# 01_Main.net
KiCad netlist of a schematic drawn in Altium Designer
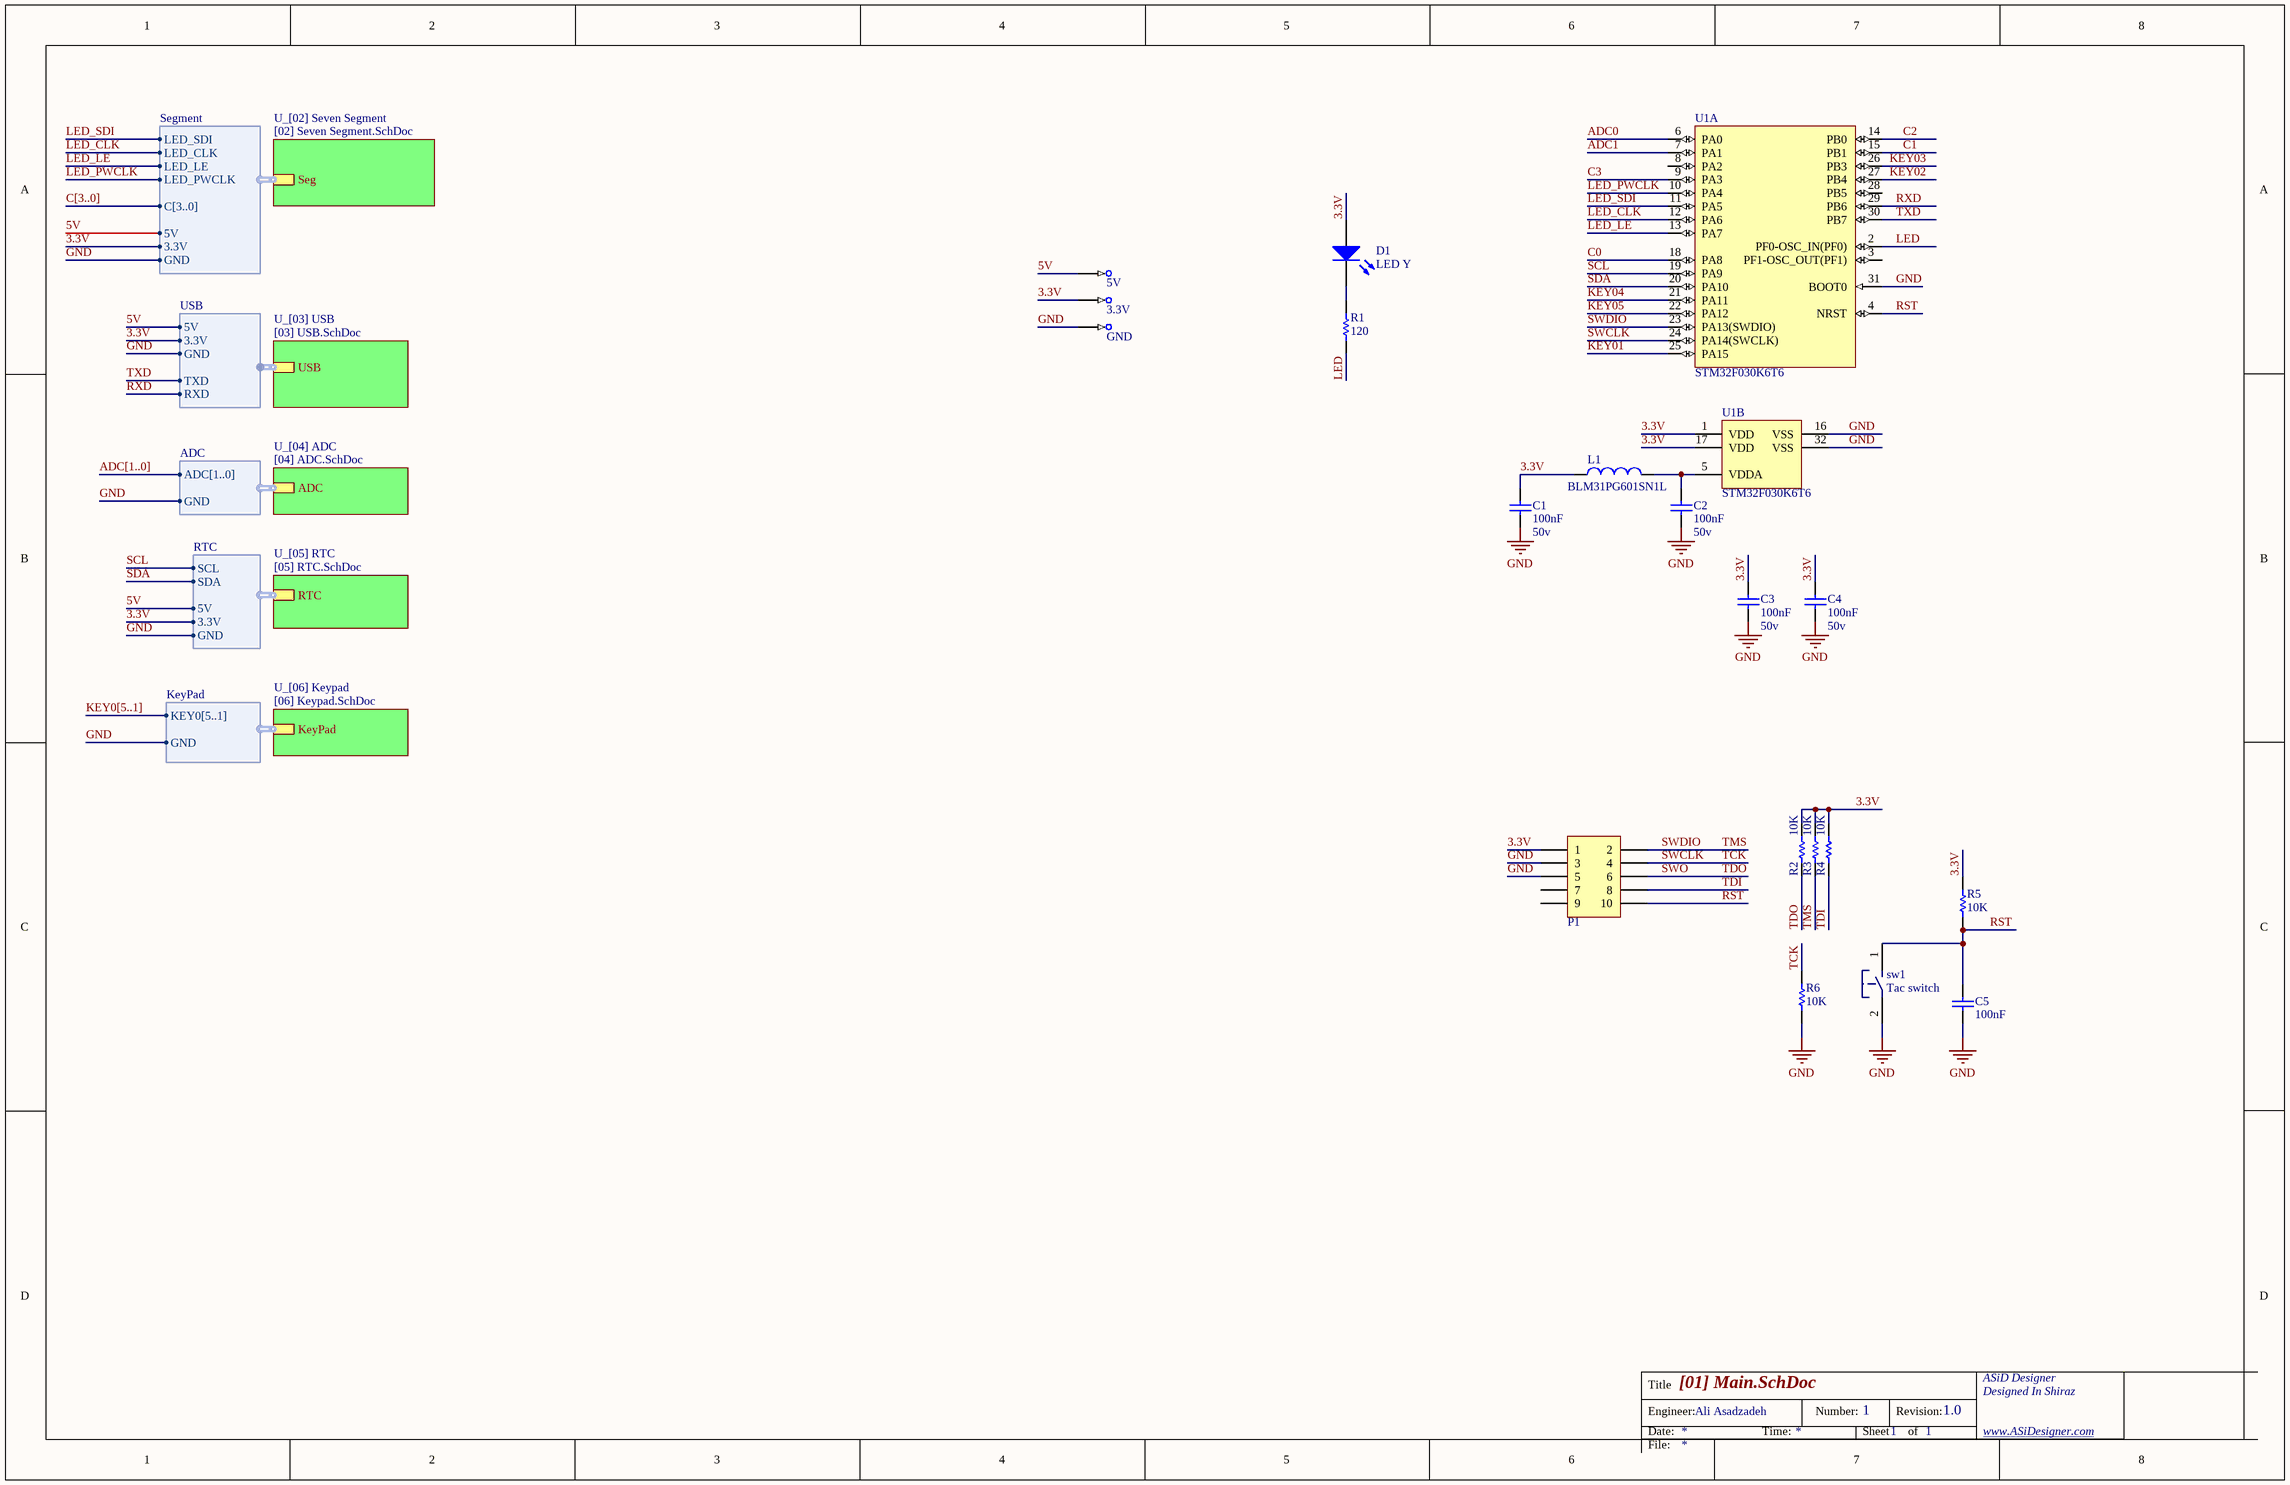
[diagram p0: [01] Main.SchDoc]

(export (version "E")
  (design (tool "Eeschema 10.0.6"))
  (components
    (comp (ref "C1")
      (value "100nF")
      (footprint "MY_0603")
      (description "None polar capacitor")
      (fields (field (name "ASID PART NUMBER") "C-AS") (field (name "VOLTE") "50v"))
      (libsource (lib "Mylib Rev 4") (part "Cap ceramic"))
    )
    (comp (ref "C2")
      (value "100nF")
      (footprint "MY_0603")
      (description "None polar capacitor")
      (fields (field (name "ASID PART NUMBER") "C-AS") (field (name "VOLTE") "50v"))
      (libsource (lib "Mylib Rev 4") (part "Cap ceramic"))
    )
    (comp (ref "C3")
      (value "100nF")
      (footprint "MY_0603")
      (description "None polar capacitor")
      (fields (field (name "ASID PART NUMBER") "C-AS") (field (name "VOLTE") "50v"))
      (libsource (lib "Mylib Rev 4") (part "Cap ceramic"))
    )
    (comp (ref "C4")
      (value "100nF")
      (footprint "MY_0603")
      (description "None polar capacitor")
      (fields (field (name "ASID PART NUMBER") "C-AS") (field (name "VOLTE") "50v"))
      (libsource (lib "Mylib Rev 4") (part "Cap ceramic"))
    )
    (comp (ref "C5")
      (value "100nF")
      (footprint "MY_0805")
      (description "CAP-100Nf")
      (libsource (lib "Mylib Rev 4") (part "Cap ceramic"))
    )
    (comp (ref "D1")
      (value "LED Y")
      (footprint "MY_LED_0805")
      (description "Typical INFRARED GaAs LED")
      (fields (field (name "ASID PART NUMBER") "LED-AS"))
      (libsource (lib "Mylib Rev 4") (part "LED"))
    )
    (comp (ref "L1")
      (value "BLM31PG601SN1L")
      (footprint "MY_1206")
      (description "Inductor")
      (fields (field (name "ASID PART NUMBER") "Inductor-AS"))
      (libsource (lib "Mylib Rev 4") (part "Inductor"))
    )
    (comp (ref "P1")
      (value "Header 5X2")
      (footprint "MY_2X05_BOX")
      (description "Header, 10-Pin, Dual row")
      (fields (field (name "ASID PART NUMBER") "Header 5X2-AS"))
      (libsource (lib "Mylib Rev 4") (part "Header 5X2"))
    )
    (comp (ref "R1")
      (value "120")
      (footprint "MY_0805")
      (description "Standard resistor")
      (fields (field (name "ASID PART NUMBER") "Res-AS"))
      (libsource (lib "Mylib Rev 4") (part "Res"))
    )
    (comp (ref "R2")
      (value "10K")
      (footprint "MY_0805")
      (description "resistor 1/4 wat")
      (libsource (lib "Mylib Rev 4") (part "Res"))
    )
    (comp (ref "R3")
      (value "10K")
      (footprint "MY_0805")
      (description "resistor 1/4 wat")
      (libsource (lib "Mylib Rev 4") (part "Res"))
    )
    (comp (ref "R4")
      (value "10K")
      (footprint "MY_0805")
      (description "resistor 1/4 wat")
      (libsource (lib "Mylib Rev 4") (part "Res"))
    )
    (comp (ref "R5")
      (value "10K")
      (footprint "MY_0805")
      (description "resistor 1/4 wat")
      (libsource (lib "Mylib Rev 4") (part "Res"))
    )
    (comp (ref "R6")
      (value "10K")
      (footprint "MY_0805")
      (description "resistor 1/4 wat")
      (libsource (lib "Mylib Rev 4") (part "Res"))
    )
    (comp (ref "sw1")
      (value "Tac switch")
      (footprint "MY_PB-SMD")
      (description "small tac switch")
      (fields (field (name "ASID PART NUMBER") "Tac switch-AS"))
      (libsource (lib "Mylib Rev 4") (part "Tac switch"))
    )
    (comp (ref "TP1")
      (value "5V")
      (footprint "MY_TestPin")
      (description "Test point")
      (fields (field (name "ASID PART NUMBER") "Test Point-AS"))
      (libsource (lib "Mylib Rev 4") (part "Test Point"))
    )
    (comp (ref "TP2")
      (value "3.3V")
      (footprint "MY_TestPin")
      (description "Test point")
      (fields (field (name "ASID PART NUMBER") "Test Point-AS"))
      (libsource (lib "Mylib Rev 4") (part "Test Point"))
    )
    (comp (ref "TP3")
      (value "GND")
      (footprint "MY_TestPin")
      (description "Test point")
      (fields (field (name "ASID PART NUMBER") "Test Point-AS"))
      (libsource (lib "Mylib Rev 4") (part "Test Point"))
    )
    (comp (ref "U1")
      (value "STM32F030K6T6")
      (footprint "STM-LQFP32_N")
      (libsource (lib "STMicroelectronics STM32 F0") (part "STM32F030K6T6"))
    )
  )
  (nets
    (net (code "5") (name "/3.3V") (class "Default")
      (node (ref "C1") (pin "2") (pinfunction "2_2") (pintype "passive"))
      (node (ref "C3") (pin "2") (pinfunction "2_2") (pintype "passive"))
      (node (ref "C4") (pin "2") (pinfunction "2_2") (pintype "passive"))
      (node (ref "D1") (pin "A") (pinfunction "A_A") (pintype "passive"))
      (node (ref "L1") (pin "1") (pinfunction "1_1") (pintype "passive"))
      (node (ref "P1") (pin "1") (pinfunction "1_1") (pintype "passive"))
      (node (ref "R2") (pin "1") (pinfunction "1_1") (pintype "passive"))
      (node (ref "R3") (pin "1") (pinfunction "1_1") (pintype "passive"))
      (node (ref "R4") (pin "1") (pinfunction "1_1") (pintype "passive"))
      (node (ref "R5") (pin "1") (pinfunction "1_1") (pintype "passive"))
      (node (ref "TP2") (pin "1") (pinfunction "1_1") (pintype "input"))
      (node (ref "U1") (pin "1") (pinfunction "VDD_1") (pintype "power_in"))
      (node (ref "U1") (pin "17") (pinfunction "VDD_17") (pintype "power_in"))
    )
    (net (code "6") (name "/5V") (class "Default")
      (node (ref "TP1") (pin "1") (pinfunction "1_1") (pintype "input"))
    )
    (net (code "7") (name "/ADC0") (class "Default")
      (node (ref "U1") (pin "6") (pinfunction "PA0_6") (pintype "bidirectional"))
    )
    (net (code "8") (name "/ADC1") (class "Default")
      (node (ref "U1") (pin "7") (pinfunction "PA1_7") (pintype "bidirectional"))
    )
    (net (code "10") (name "/C0") (class "Default")
      (node (ref "U1") (pin "18") (pinfunction "PA8_18") (pintype "bidirectional"))
    )
    (net (code "11") (name "/C1") (class "Default")
      (node (ref "U1") (pin "15") (pinfunction "PB1_15") (pintype "bidirectional"))
    )
    (net (code "12") (name "/C2") (class "Default")
      (node (ref "U1") (pin "14") (pinfunction "PB0_14") (pintype "bidirectional"))
    )
    (net (code "13") (name "/C3") (class "Default")
      (node (ref "U1") (pin "9") (pinfunction "PA3_9") (pintype "bidirectional"))
    )
    (net (code "15") (name "/KEY01") (class "Default")
      (node (ref "U1") (pin "25") (pinfunction "PA15_25") (pintype "bidirectional"))
    )
    (net (code "16") (name "/KEY02") (class "Default")
      (node (ref "U1") (pin "27") (pinfunction "PB4_27") (pintype "bidirectional"))
    )
    (net (code "17") (name "/KEY03") (class "Default")
      (node (ref "U1") (pin "26") (pinfunction "PB3_26") (pintype "bidirectional"))
    )
    (net (code "18") (name "/KEY04") (class "Default")
      (node (ref "U1") (pin "21") (pinfunction "PA11_21") (pintype "bidirectional"))
    )
    (net (code "19") (name "/KEY05") (class "Default")
      (node (ref "U1") (pin "22") (pinfunction "PA12_22") (pintype "bidirectional"))
    )
    (net (code "21") (name "/LED") (class "Default")
      (node (ref "R1") (pin "1") (pinfunction "1_1") (pintype "passive"))
      (node (ref "U1") (pin "2") (pinfunction "PF0-OSC_IN(PF0)_2") (pintype "bidirectional"))
    )
    (net (code "22") (name "/LED_CLK") (class "Default")
      (node (ref "U1") (pin "12") (pinfunction "PA6_12") (pintype "bidirectional"))
    )
    (net (code "23") (name "/LED_LE") (class "Default")
      (node (ref "U1") (pin "13") (pinfunction "PA7_13") (pintype "bidirectional"))
    )
    (net (code "24") (name "/LED_PWCLK") (class "Default")
      (node (ref "U1") (pin "10") (pinfunction "PA4_10") (pintype "bidirectional"))
    )
    (net (code "25") (name "/LED_SDI") (class "Default")
      (node (ref "U1") (pin "11") (pinfunction "PA5_11") (pintype "bidirectional"))
    )
    (net (code "26") (name "/RST") (class "Default")
      (node (ref "C5") (pin "2") (pinfunction "2_2") (pintype "passive"))
      (node (ref "P1") (pin "10") (pinfunction "10_10") (pintype "passive"))
      (node (ref "R5") (pin "2") (pinfunction "2_2") (pintype "passive"))
      (node (ref "U1") (pin "4") (pinfunction "NRST_4") (pintype "bidirectional"))
      (node (ref "sw1") (pin "1") (pinfunction "1_1") (pintype "passive"))
    )
    (net (code "27") (name "/RXD") (class "Default")
      (node (ref "U1") (pin "29") (pinfunction "PB6_29") (pintype "bidirectional"))
    )
    (net (code "28") (name "/SCL") (class "Default")
      (node (ref "U1") (pin "19") (pinfunction "PA9_19") (pintype "bidirectional"))
    )
    (net (code "29") (name "/SDA") (class "Default")
      (node (ref "U1") (pin "20") (pinfunction "PA10_20") (pintype "bidirectional"))
    )
    (net (code "30") (name "/SWCLK") (class "Default")
      (node (ref "P1") (pin "4") (pinfunction "4_4") (pintype "passive"))
      (node (ref "R6") (pin "1") (pinfunction "1_1") (pintype "passive"))
      (node (ref "U1") (pin "24") (pinfunction "PA14(SWCLK)_24") (pintype "bidirectional"))
    )
    (net (code "31") (name "/SWDIO") (class "Default")
      (node (ref "P1") (pin "2") (pinfunction "2_2") (pintype "passive"))
      (node (ref "R3") (pin "2") (pinfunction "2_2") (pintype "passive"))
      (node (ref "U1") (pin "23") (pinfunction "PA13(SWDIO)_23") (pintype "bidirectional"))
    )
    (net (code "32") (name "/SWO") (class "Default")
      (node (ref "P1") (pin "6") (pinfunction "6_6") (pintype "passive"))
      (node (ref "R2") (pin "2") (pinfunction "2_2") (pintype "passive"))
    )
    (net (code "33") (name "/TDI") (class "Default")
      (node (ref "P1") (pin "8") (pinfunction "8_8") (pintype "passive"))
      (node (ref "R4") (pin "2") (pinfunction "2_2") (pintype "passive"))
    )
    (net (code "34") (name "/TXD") (class "Default")
      (node (ref "U1") (pin "30") (pinfunction "PB7_30") (pintype "bidirectional"))
    )
    (net (code "40") (name "GND") (class "Default")
      (node (ref "C1") (pin "1") (pinfunction "1_1") (pintype "passive"))
      (node (ref "C2") (pin "1") (pinfunction "1_1") (pintype "passive"))
      (node (ref "C3") (pin "1") (pinfunction "1_1") (pintype "passive"))
      (node (ref "C4") (pin "1") (pinfunction "1_1") (pintype "passive"))
      (node (ref "C5") (pin "1") (pinfunction "1_1") (pintype "passive"))
      (node (ref "P1") (pin "3") (pinfunction "3_3") (pintype "passive"))
      (node (ref "P1") (pin "5") (pinfunction "5_5") (pintype "passive"))
      (node (ref "R6") (pin "2") (pinfunction "2_2") (pintype "passive"))
      (node (ref "TP3") (pin "1") (pinfunction "1_1") (pintype "input"))
      (node (ref "U1") (pin "16") (pinfunction "VSS_16") (pintype "power_in"))
      (node (ref "U1") (pin "31") (pinfunction "BOOT0_31") (pintype "input"))
      (node (ref "U1") (pin "32") (pinfunction "VSS_32") (pintype "power_in"))
      (node (ref "sw1") (pin "2") (pinfunction "2_2") (pintype "passive"))
    )
    (net (code "41") (name "Net-(D1-PadK)") (class "Default")
      (node (ref "D1") (pin "K") (pinfunction "K_K") (pintype "passive"))
      (node (ref "R1") (pin "2") (pinfunction "2_2") (pintype "passive"))
    )
    (net (code "42") (name "Net-(U1B-VDDA)") (class "Default")
      (node (ref "C2") (pin "2") (pinfunction "2_2") (pintype "passive"))
      (node (ref "L1") (pin "2") (pinfunction "2_2") (pintype "passive"))
      (node (ref "U1") (pin "5") (pinfunction "VDDA_5") (pintype "power_in"))
    )
    (net (code "43") (name "unconnected-(P1-Pad7)") (class "Default")
      (node (ref "P1") (pin "7") (pinfunction "7_7") (pintype "passive"))
    )
    (net (code "44") (name "unconnected-(P1-Pad9)") (class "Default")
      (node (ref "P1") (pin "9") (pinfunction "9_9") (pintype "passive"))
    )
    (net (code "45") (name "unconnected-(U1A-PA2-Pad8)") (class "Default")
      (node (ref "U1") (pin "8") (pinfunction "PA2_8") (pintype "bidirectional"))
    )
    (net (code "46") (name "unconnected-(U1A-PB5-Pad28)") (class "Default")
      (node (ref "U1") (pin "28") (pinfunction "PB5_28") (pintype "bidirectional"))
    )
    (net (code "47") (name "unconnected-(U1A-PF1-OSC_OUT(PF1)-Pad3)") (class "Default")
      (node (ref "U1") (pin "3") (pinfunction "PF1-OSC_OUT(PF1)_3") (pintype "bidirectional"))
    )
  )
)
